# RFM73_Cape.net
KiCad netlist of a schematic drawn in EAGLE
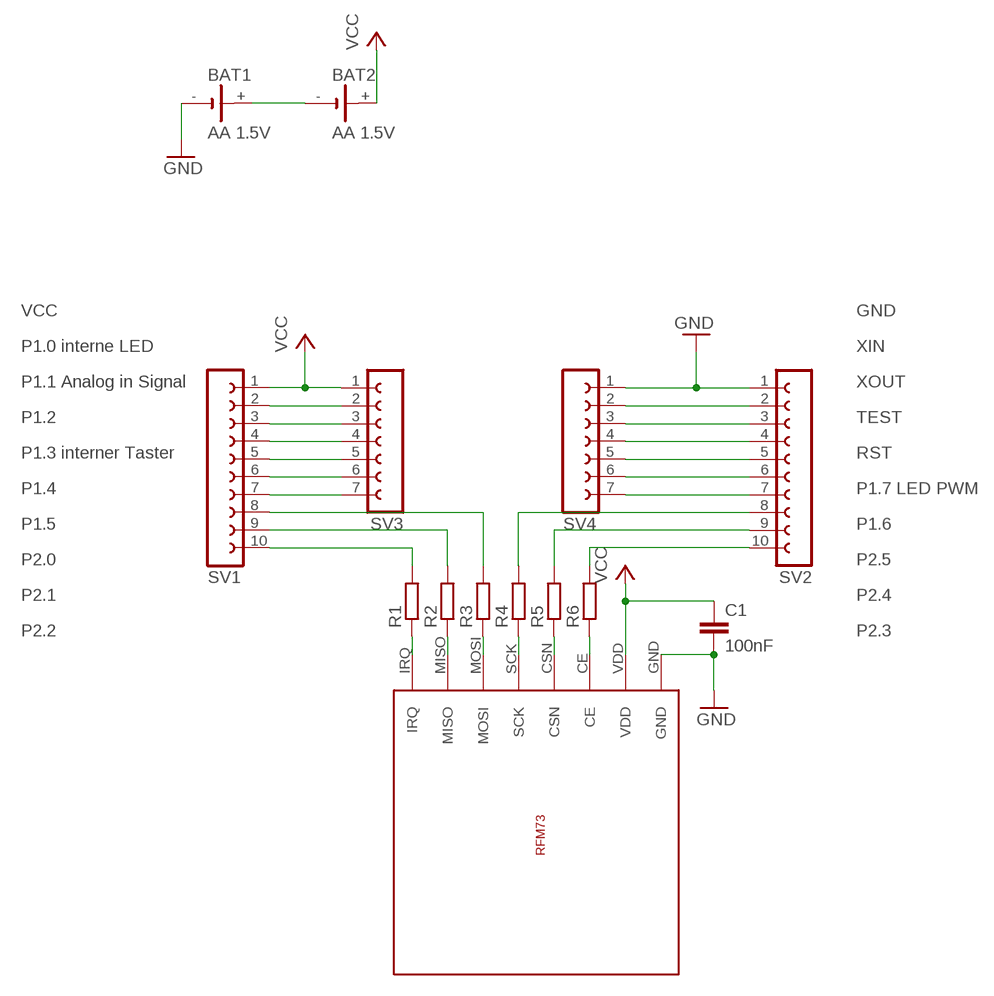
[diagram p0: schematic, sheet 1]

(export (version "E")
  (design (tool "Eeschema 10.0.6"))
  (components
    (comp (ref "BAT1")
      (value "AA 1.5V")
      (footprint "eagle-import:SL-160AA_PR")
      (libsource (lib "eagle-import") (part "SL-160AA/PR"))
    )
    (comp (ref "BAT2")
      (value "AA 1.5V")
      (footprint "eagle-import:SL-160AA_PR")
      (libsource (lib "eagle-import") (part "SL-160AA/PR"))
    )
    (comp (ref "C1")
      (value "100nF")
      (footprint "eagle-import:C0805")
      (libsource (lib "eagle-import") (part "C-EUC0805"))
    )
    (comp (ref "R1")
      (value "R-EU_R0805W")
      (footprint "eagle-import:R0805W")
      (libsource (lib "eagle-import") (part "R-EU_R0805W"))
    )
    (comp (ref "R2")
      (value "R-EU_R0805W")
      (footprint "eagle-import:R0805W")
      (libsource (lib "eagle-import") (part "R-EU_R0805W"))
    )
    (comp (ref "R3")
      (value "R-EU_R0805W")
      (footprint "eagle-import:R0805W")
      (libsource (lib "eagle-import") (part "R-EU_R0805W"))
    )
    (comp (ref "R4")
      (value "R-EU_R0805W")
      (footprint "eagle-import:R0805W")
      (libsource (lib "eagle-import") (part "R-EU_R0805W"))
    )
    (comp (ref "R5")
      (value "R-EU_R0805W")
      (footprint "eagle-import:R0805W")
      (libsource (lib "eagle-import") (part "R-EU_R0805W"))
    )
    (comp (ref "R6")
      (value "R-EU_R0805W")
      (footprint "eagle-import:R0805W")
      (libsource (lib "eagle-import") (part "R-EU_R0805W"))
    )
    (comp (ref "SV1")
      (value "FE10-1")
      (footprint "eagle-import:FE10")
      (libsource (lib "eagle-import") (part "FE10-1"))
    )
    (comp (ref "SV2")
      (value "FE10-1")
      (footprint "eagle-import:FE10")
      (libsource (lib "eagle-import") (part "FE10-1"))
    )
    (comp (ref "SV3")
      (value "FE07-1")
      (footprint "eagle-import:FE07")
      (libsource (lib "eagle-import") (part "FE07-1"))
    )
    (comp (ref "SV4")
      (value "FE07-1")
      (footprint "eagle-import:FE07")
      (libsource (lib "eagle-import") (part "FE07-1"))
    )
    (comp (ref "U$1")
      (value "RFM73")
      (footprint "eagle-import:RFM73")
      (libsource (lib "eagle-import") (part "RFM73"))
    )
  )
  (nets
    (net (code "1") (name "GND") (class "Default")
      (node (ref "BAT1") (pin "-") (pinfunction "-_-") (pintype "passive"))
      (node (ref "C1") (pin "2") (pinfunction "2_2") (pintype "passive"))
      (node (ref "SV2") (pin "1") (pinfunction "1_1") (pintype "passive"))
      (node (ref "SV4") (pin "1") (pinfunction "1_1") (pintype "passive"))
      (node (ref "U$1") (pin "GND") (pinfunction "GND_GND") (pintype "bidirectional"))
    )
    (net (code "2") (name "Net-(BAT1-Pad+)") (class "Default")
      (node (ref "BAT1") (pin "+") (pinfunction "+_+") (pintype "passive"))
      (node (ref "BAT2") (pin "-") (pinfunction "-_-") (pintype "passive"))
    )
    (net (code "3") (name "Net-(R1-Pad1)") (class "Default")
      (node (ref "R1") (pin "1") (pinfunction "1_1") (pintype "passive"))
      (node (ref "U$1") (pin "IRQ") (pinfunction "IRQ_IRQ") (pintype "bidirectional"))
    )
    (net (code "4") (name "Net-(R1-Pad2)") (class "Default")
      (node (ref "R1") (pin "2") (pinfunction "2_2") (pintype "passive"))
      (node (ref "SV1") (pin "10") (pinfunction "10_10") (pintype "passive"))
    )
    (net (code "5") (name "Net-(R2-Pad1)") (class "Default")
      (node (ref "R2") (pin "1") (pinfunction "1_1") (pintype "passive"))
      (node (ref "U$1") (pin "MISO") (pinfunction "MISO_MISO") (pintype "bidirectional"))
    )
    (net (code "6") (name "Net-(R2-Pad2)") (class "Default")
      (node (ref "R2") (pin "2") (pinfunction "2_2") (pintype "passive"))
      (node (ref "SV1") (pin "9") (pinfunction "9_9") (pintype "passive"))
    )
    (net (code "7") (name "Net-(R3-Pad1)") (class "Default")
      (node (ref "R3") (pin "1") (pinfunction "1_1") (pintype "passive"))
      (node (ref "U$1") (pin "MOSI") (pinfunction "MOSI_MOSI") (pintype "bidirectional"))
    )
    (net (code "8") (name "Net-(R3-Pad2)") (class "Default")
      (node (ref "R3") (pin "2") (pinfunction "2_2") (pintype "passive"))
      (node (ref "SV1") (pin "8") (pinfunction "8_8") (pintype "passive"))
    )
    (net (code "9") (name "Net-(R4-Pad1)") (class "Default")
      (node (ref "R4") (pin "1") (pinfunction "1_1") (pintype "passive"))
      (node (ref "U$1") (pin "SCK") (pinfunction "SCK_SCK") (pintype "bidirectional"))
    )
    (net (code "10") (name "Net-(R4-Pad2)") (class "Default")
      (node (ref "R4") (pin "2") (pinfunction "2_2") (pintype "passive"))
      (node (ref "SV2") (pin "8") (pinfunction "8_8") (pintype "passive"))
    )
    (net (code "11") (name "Net-(R5-Pad1)") (class "Default")
      (node (ref "R5") (pin "1") (pinfunction "1_1") (pintype "passive"))
      (node (ref "U$1") (pin "CSN") (pinfunction "CSN_CSN") (pintype "bidirectional"))
    )
    (net (code "12") (name "Net-(R5-Pad2)") (class "Default")
      (node (ref "R5") (pin "2") (pinfunction "2_2") (pintype "passive"))
      (node (ref "SV2") (pin "9") (pinfunction "9_9") (pintype "passive"))
    )
    (net (code "13") (name "Net-(R6-Pad1)") (class "Default")
      (node (ref "R6") (pin "1") (pinfunction "1_1") (pintype "passive"))
      (node (ref "U$1") (pin "CE") (pinfunction "CE_CE") (pintype "bidirectional"))
    )
    (net (code "14") (name "Net-(R6-Pad2)") (class "Default")
      (node (ref "R6") (pin "2") (pinfunction "2_2") (pintype "passive"))
      (node (ref "SV2") (pin "10") (pinfunction "10_10") (pintype "passive"))
    )
    (net (code "15") (name "Net-(SV1-Pad2)") (class "Default")
      (node (ref "SV1") (pin "2") (pinfunction "2_2") (pintype "passive"))
      (node (ref "SV3") (pin "2") (pinfunction "2_2") (pintype "passive"))
    )
    (net (code "16") (name "Net-(SV1-Pad3)") (class "Default")
      (node (ref "SV1") (pin "3") (pinfunction "3_3") (pintype "passive"))
      (node (ref "SV3") (pin "3") (pinfunction "3_3") (pintype "passive"))
    )
    (net (code "17") (name "Net-(SV1-Pad4)") (class "Default")
      (node (ref "SV1") (pin "4") (pinfunction "4_4") (pintype "passive"))
      (node (ref "SV3") (pin "4") (pinfunction "4_4") (pintype "passive"))
    )
    (net (code "18") (name "Net-(SV1-Pad5)") (class "Default")
      (node (ref "SV1") (pin "5") (pinfunction "5_5") (pintype "passive"))
      (node (ref "SV3") (pin "5") (pinfunction "5_5") (pintype "passive"))
    )
    (net (code "19") (name "Net-(SV1-Pad6)") (class "Default")
      (node (ref "SV1") (pin "6") (pinfunction "6_6") (pintype "passive"))
      (node (ref "SV3") (pin "6") (pinfunction "6_6") (pintype "passive"))
    )
    (net (code "20") (name "Net-(SV1-Pad7)") (class "Default")
      (node (ref "SV1") (pin "7") (pinfunction "7_7") (pintype "passive"))
      (node (ref "SV3") (pin "7") (pinfunction "7_7") (pintype "passive"))
    )
    (net (code "21") (name "Net-(SV2-Pad2)") (class "Default")
      (node (ref "SV2") (pin "2") (pinfunction "2_2") (pintype "passive"))
      (node (ref "SV4") (pin "2") (pinfunction "2_2") (pintype "passive"))
    )
    (net (code "22") (name "Net-(SV2-Pad3)") (class "Default")
      (node (ref "SV2") (pin "3") (pinfunction "3_3") (pintype "passive"))
      (node (ref "SV4") (pin "3") (pinfunction "3_3") (pintype "passive"))
    )
    (net (code "23") (name "Net-(SV2-Pad4)") (class "Default")
      (node (ref "SV2") (pin "4") (pinfunction "4_4") (pintype "passive"))
      (node (ref "SV4") (pin "4") (pinfunction "4_4") (pintype "passive"))
    )
    (net (code "24") (name "Net-(SV2-Pad5)") (class "Default")
      (node (ref "SV2") (pin "5") (pinfunction "5_5") (pintype "passive"))
      (node (ref "SV4") (pin "5") (pinfunction "5_5") (pintype "passive"))
    )
    (net (code "25") (name "Net-(SV2-Pad6)") (class "Default")
      (node (ref "SV2") (pin "6") (pinfunction "6_6") (pintype "passive"))
      (node (ref "SV4") (pin "6") (pinfunction "6_6") (pintype "passive"))
    )
    (net (code "26") (name "Net-(SV2-Pad7)") (class "Default")
      (node (ref "SV2") (pin "7") (pinfunction "7_7") (pintype "passive"))
      (node (ref "SV4") (pin "7") (pinfunction "7_7") (pintype "passive"))
    )
    (net (code "27") (name "VCC") (class "Default")
      (node (ref "BAT2") (pin "+") (pinfunction "+_+") (pintype "passive"))
      (node (ref "C1") (pin "1") (pinfunction "1_1") (pintype "passive"))
      (node (ref "SV1") (pin "1") (pinfunction "1_1") (pintype "passive"))
      (node (ref "SV3") (pin "1") (pinfunction "1_1") (pintype "passive"))
      (node (ref "U$1") (pin "VDD") (pinfunction "VDD_VDD") (pintype "bidirectional"))
    )
  )
)
